# Servant.net
KiCad netlist of a schematic drawn in EAGLE
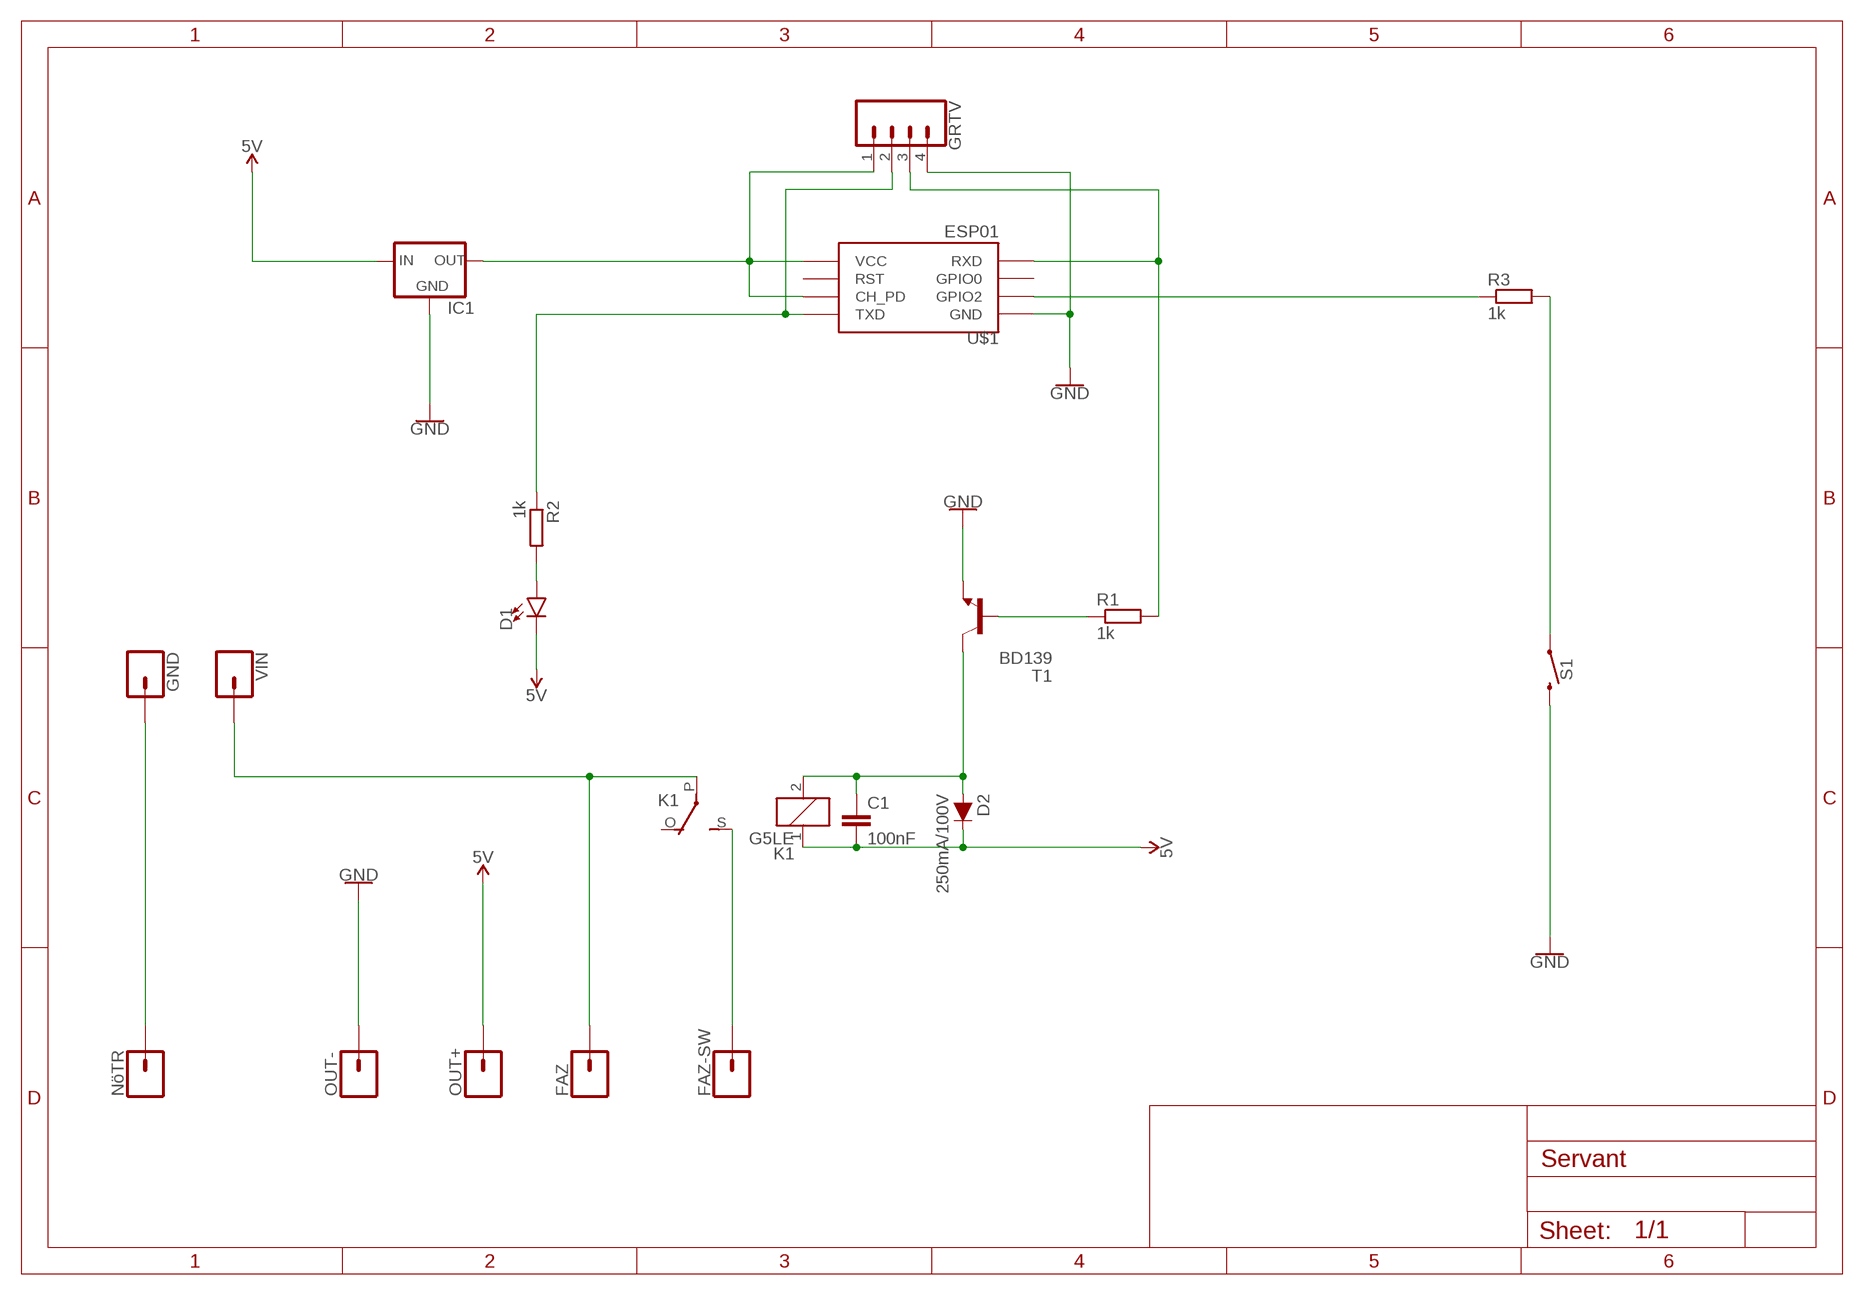
[diagram p0: schematic, sheet 1]

(export (version "E")
  (design (tool "Eeschema 10.0.6"))
  (components
    (comp (ref "C1")
      (value "100nF")
      (footprint "eagle-import:0805")
      (libsource (lib "eagle-import") (part "22UF-0805-6.3V-20%"))
    )
    (comp (ref "D1")
      (value "LED-3MM-NO_SILK")
      (footprint "eagle-import:LED_3MM-NS")
      (libsource (lib "eagle-import") (part "LED-3MM-NO_SILK"))
    )
    (comp (ref "D2")
      (value "250mA/100V")
      (footprint "eagle-import:SOD-323")
      (libsource (lib "eagle-import") (part "DIODE-BAS16J"))
    )
    (comp (ref "FAZ")
      (value "CONN_01PTH_LONGPAD")
      (footprint "eagle-import:1X01_LONGPAD")
      (libsource (lib "eagle-import") (part "CONN_01PTH_LONGPAD"))
    )
    (comp (ref "FAZ-SW")
      (value "CONN_01PTH_LONGPAD")
      (footprint "eagle-import:1X01_LONGPAD")
      (libsource (lib "eagle-import") (part "CONN_01PTH_LONGPAD"))
    )
    (comp (ref "GND")
      (value "CONN_01")
      (footprint "eagle-import:1X01")
      (libsource (lib "eagle-import") (part "CONN_01"))
    )
    (comp (ref "GRTV")
      (value "CONN_041X04_NO_SILK")
      (footprint "eagle-import:1X04_NO_SILK")
      (libsource (lib "eagle-import") (part "CONN_041X04_NO_SILK"))
    )
    (comp (ref "IC1")
      (value "XC63FPM")
      (footprint "eagle-import:SOT23")
      (libsource (lib "eagle-import") (part "XC63FPM"))
    )
    (comp (ref "K1")
      (value "G5LE")
      (footprint "eagle-import:G5LE")
      (libsource (lib "eagle-import") (part "G5LE"))
    )
    (comp (ref "NöTR")
      (value "CONN_01PTH_LONGPAD")
      (footprint "eagle-import:1X01_LONGPAD")
      (libsource (lib "eagle-import") (part "CONN_01PTH_LONGPAD"))
    )
    (comp (ref "OUT+")
      (value "CONN_01")
      (footprint "eagle-import:1X01")
      (libsource (lib "eagle-import") (part "CONN_01"))
    )
    (comp (ref "OUT-")
      (value "CONN_01")
      (footprint "eagle-import:1X01")
      (libsource (lib "eagle-import") (part "CONN_01"))
    )
    (comp (ref "R1")
      (value "1k")
      (footprint "eagle-import:R1206")
      (libsource (lib "eagle-import") (part "R-EU_R1206"))
    )
    (comp (ref "R2")
      (value "1k")
      (footprint "eagle-import:R1206")
      (libsource (lib "eagle-import") (part "R-EU_R1206"))
    )
    (comp (ref "R3")
      (value "1k")
      (footprint "eagle-import:R1206")
      (libsource (lib "eagle-import") (part "R-EU_R1206"))
    )
    (comp (ref "S1")
      (value "MOMENTARY-SWITCH-SPST-PTH-6.0MM")
      (footprint "eagle-import:TACTILE_SWITCH_PTH_6.0MM")
      (libsource (lib "eagle-import") (part "MOMENTARY-SWITCH-SPST-PTH-6.0MM"))
    )
    (comp (ref "T1")
      (value "BD139")
      (footprint "eagle-import:TO126V")
      (libsource (lib "eagle-import") (part "-NPN-TO126V"))
    )
    (comp (ref "U$1")
      (value "ESP01")
      (footprint "eagle-import:ESP01")
      (libsource (lib "eagle-import") (part "ESP01"))
    )
    (comp (ref "VIN")
      (value "CONN_01")
      (footprint "eagle-import:1X01")
      (libsource (lib "eagle-import") (part "CONN_01"))
    )
  )
  (nets
    (net (code "1") (name "5V") (class "Default")
      (node (ref "C1") (pin "2") (pinfunction "2_2") (pintype "passive"))
      (node (ref "D1") (pin "K") (pinfunction "C_K") (pintype "passive"))
      (node (ref "D2") (pin "C") (pinfunction "C_C") (pintype "passive"))
      (node (ref "IC1") (pin "3") (pinfunction "IN_3") (pintype "input"))
      (node (ref "K1") (pin "1") (pinfunction "1_1") (pintype "passive"))
      (node (ref "OUT+") (pin "1") (pinfunction "1_1") (pintype "passive"))
    )
    (net (code "2") (name "GND") (class "Default")
      (node (ref "GRTV") (pin "4") (pinfunction "4_4") (pintype "passive"))
      (node (ref "IC1") (pin "1") (pinfunction "GND_1") (pintype "input"))
      (node (ref "OUT-") (pin "1") (pinfunction "1_1") (pintype "passive"))
      (node (ref "S1") (pin "3") (pinfunction "2_3") (pintype "passive"))
      (node (ref "T1") (pin "1") (pinfunction "E_1") (pintype "passive"))
      (node (ref "U$1") (pin "GND") (pinfunction "GND_GND") (pintype "bidirectional"))
    )
    (net (code "3") (name "Net-(D1-PadA)") (class "Default")
      (node (ref "D1") (pin "A") (pinfunction "A_A") (pintype "passive"))
      (node (ref "R2") (pin "2") (pinfunction "2_2") (pintype "passive"))
    )
    (net (code "4") (name "Net-(FAZ-Pad1)") (class "Default")
      (node (ref "FAZ") (pin "1") (pinfunction "1_1") (pintype "passive"))
      (node (ref "K1") (pin "P") (pinfunction "P_P") (pintype "passive"))
      (node (ref "VIN") (pin "1") (pinfunction "1_1") (pintype "passive"))
    )
    (net (code "5") (name "Net-(FAZ-SW-Pad1)") (class "Default")
      (node (ref "FAZ-SW") (pin "1") (pinfunction "1_1") (pintype "passive"))
      (node (ref "K1") (pin "S") (pinfunction "S_S") (pintype "passive"))
    )
    (net (code "6") (name "Net-(GND-Pad1)") (class "Default")
      (node (ref "GND") (pin "1") (pinfunction "1_1") (pintype "passive"))
      (node (ref "NöTR") (pin "1") (pinfunction "1_1") (pintype "passive"))
    )
    (net (code "7") (name "Net-(IC1-OUT)") (class "Default")
      (node (ref "GRTV") (pin "1") (pinfunction "1_1") (pintype "passive"))
      (node (ref "IC1") (pin "2") (pinfunction "OUT_2") (pintype "passive"))
      (node (ref "U$1") (pin "CH_PD") (pinfunction "CH_PD_CH_PD") (pintype "bidirectional"))
      (node (ref "U$1") (pin "VCC") (pinfunction "VCC_VCC") (pintype "bidirectional"))
    )
    (net (code "8") (name "Net-(R3-Pad1)") (class "Default")
      (node (ref "R3") (pin "1") (pinfunction "1_1") (pintype "passive"))
      (node (ref "U$1") (pin "GPIO2") (pinfunction "GPIO2_GPIO2") (pintype "bidirectional"))
    )
    (net (code "9") (name "Net-(R3-Pad2)") (class "Default")
      (node (ref "R3") (pin "2") (pinfunction "2_2") (pintype "passive"))
      (node (ref "S1") (pin "1") (pinfunction "1_1") (pintype "passive"))
    )
    (net (code "10") (name "Net-(T1-B)") (class "Default")
      (node (ref "R1") (pin "1") (pinfunction "1_1") (pintype "passive"))
      (node (ref "T1") (pin "3") (pinfunction "B_3") (pintype "passive"))
    )
    (net (code "11") (name "Net-(T1-C)") (class "Default")
      (node (ref "C1") (pin "1") (pinfunction "1_1") (pintype "passive"))
      (node (ref "D2") (pin "A") (pinfunction "A_A") (pintype "passive"))
      (node (ref "K1") (pin "2") (pinfunction "2_2") (pintype "passive"))
      (node (ref "T1") (pin "2") (pinfunction "C_2") (pintype "passive"))
    )
    (net (code "12") (name "Net-(U$1-RXD)") (class "Default")
      (node (ref "GRTV") (pin "3") (pinfunction "3_3") (pintype "passive"))
      (node (ref "R1") (pin "2") (pinfunction "2_2") (pintype "passive"))
      (node (ref "U$1") (pin "RX") (pinfunction "RXD_RX") (pintype "bidirectional"))
    )
    (net (code "13") (name "Net-(U$1-TXD)") (class "Default")
      (node (ref "GRTV") (pin "2") (pinfunction "2_2") (pintype "passive"))
      (node (ref "R2") (pin "1") (pinfunction "1_1") (pintype "passive"))
      (node (ref "U$1") (pin "TX") (pinfunction "TXD_TX") (pintype "bidirectional"))
    )
    (net (code "14") (name "unconnected-(K1-PadO)") (class "Default")
      (node (ref "K1") (pin "O") (pinfunction "O_O") (pintype "passive"))
    )
    (net (code "15") (name "unconnected-(U$1-PadGPIO0)") (class "Default")
      (node (ref "U$1") (pin "GPIO0") (pinfunction "GPIO0_GPIO0") (pintype "bidirectional"))
    )
    (net (code "16") (name "unconnected-(U$1-PadRST)") (class "Default")
      (node (ref "U$1") (pin "RST") (pinfunction "RST_RST") (pintype "bidirectional"))
    )
  )
)
